# SensorSchem.net
KiCad netlist of a schematic drawn in Altium Designer
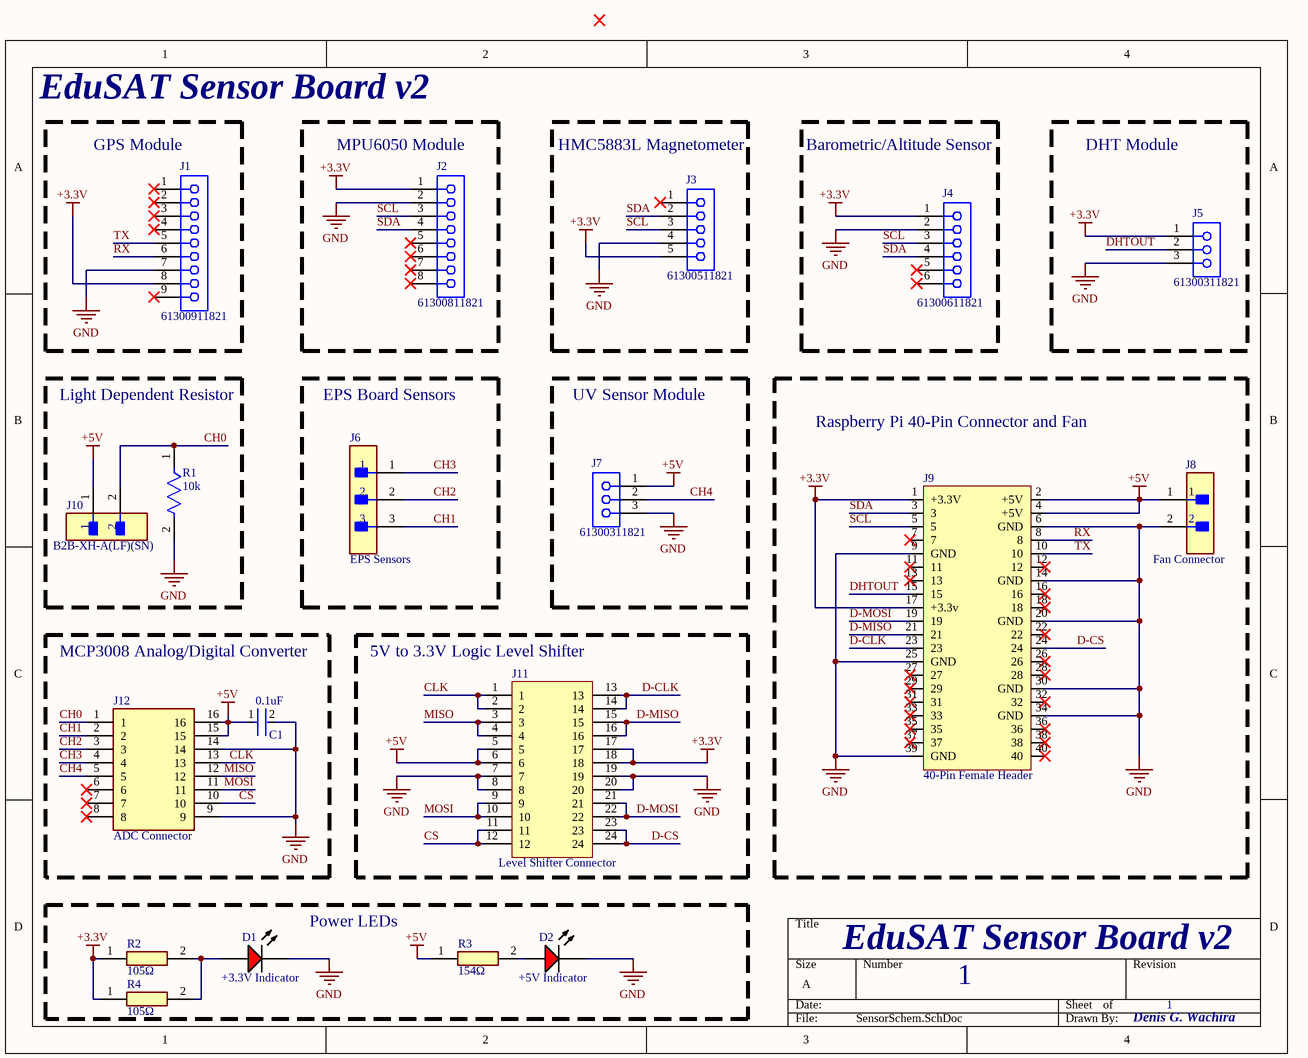
[diagram p0: SensorSchem.SchDoc]

(export (version "E")
  (design (tool "Eeschema 10.0.6"))
  (components
    (comp (ref "C1")
      (value "0.1uF")
      (footprint "FP-CL21-IPC_A")
      (description "50V 0.1uF X7R ±10% 0805 Multilayer Ceramic Capacitors MLCC - SMD/SMT ROHS TCC0805X7R104K500DT")
      (fields (field (name "TOLERANCE") "10%"))
      (libsource (lib "Altium Content Vault") (part "b4654b650e69147ec39a6b967a45e02"))
    )
    (comp (ref "D1")
      (value "+3.3V Indicator")
      (footprint "LTST-C170KRKT_V")
      (description "LED Red,KT-0805R")
      (fields (field (name "MANUFACTURER") "Lite-On"))
      (libsource (lib "Altium Content Vault") (part "LED-RED-AK-2"))
    )
    (comp (ref "D2")
      (value "+5V Indicator")
      (footprint "LTST-C170KRKT_V")
      (description "LED Red,KT-0805R")
      (fields (field (name "MANUFACTURER") "Lite-On"))
      (libsource (lib "Altium Content Vault") (part "LED-RED-AK-2"))
    )
    (comp (ref "J1")
      (value "61300911821")
      (footprint "61300911821")
      (libsource (lib "Altium Content Vault") (part "Header_Female_1R_09P"))
    )
    (comp (ref "J2")
      (value "61300811821")
      (footprint "61300811821")
      (libsource (lib "Altium Content Vault") (part "Header_Female_1R_08P"))
    )
    (comp (ref "J3")
      (value "61300511821")
      (footprint "61300511821")
      (libsource (lib "Altium Content Vault") (part "Header_Female_1R_05P"))
    )
    (comp (ref "J4")
      (value "61300611821")
      (footprint "61300611821")
      (libsource (lib "Altium Content Vault") (part "Header_Female_1R_06P"))
    )
    (comp (ref "J5")
      (value "61300311821")
      (footprint "61300311821")
      (libsource (lib "Altium Content Vault") (part "Header_Female_1R_03P"))
    )
    (comp (ref "J6")
      (value "EPS Sensors")
      (footprint "FP-S3B-XH-A-1_LF_SN-MFG")
      (description "CONN HEADER R/A 3POS 2.5MM \r\nHCZZ0139-3")
      (libsource (lib "Altium Content Vault") (part "0d3f023dd272f625e17a2be33dea85f"))
    )
    (comp (ref "J7")
      (value "61300311821")
      (footprint "61300311821")
      (libsource (lib "Altium Content Vault") (part "Header_Female_1R_03P"))
    )
    (comp (ref "J8")
      (value "Fan Connector")
      (footprint "FP-B2B-XH-A_LF_SN-MFG")
      (description "CONN HEADER VERT 2POS 2.5MM")
      (libsource (lib "Altium Content Vault") (part "3bc925449376181038e59eaffc5286c"))
    )
    (comp (ref "J9")
      (value "40-Pin Female Header")
      (footprint "FP-7-534206-0-MFG")
      (libsource (lib "University of Nairobi") (part "40-Pin Female Header"))
    )
    (comp (ref "J10")
      (value "B2B-XH-A(LF)(SN)")
      (footprint "FP-B2B-XH-A_LF_SN-MFG")
      (description "CONN HEADER VERT 2POS 2.5MM")
      (libsource (lib "") (part "3bc925449376181038e59eaffc5286c_1"))
    )
    (comp (ref "J11")
      (value "Level Shifter Connector")
      (footprint "61301221821")
      (description "3.3V to 5V Level Shifter Connector")
      (libsource (lib "University of Nairobi") (part "Level Shifter"))
    )
    (comp (ref "J12")
      (value "ADC Connector")
      (footprint "AMPHENOL_DILB16P-223TLF")
      (description "DIP Socket, Stamped and Formed")
      (fields (field (name "MP") "DILB16P-223TLF") (field (name "MF") "Amphenol ICC (FCI)"))
      (libsource (lib "University of Nairobi") (part "DILB16P-223TLF"))
    )
    (comp (ref "R1")
      (value "10k")
      (footprint "FP-MCR10-IPC_C")
      (description "Thick Film Chip Resistor, 0805, 10kΩ, 1%, 100ppm/°C, 0.125W, 150V \r\n0805W8F1002T5E")
      (fields (field (name "TOLERANCE") "1%"))
      (libsource (lib "Altium Content Vault") (part "1029c3af85768c4190bb7ad29bc67b5"))
    )
    (comp (ref "R2")
      (value "105Ω")
      (footprint "SamacSys:RESC2012X65N")
      (fields (field (name "MANUFACTURER_PART_NUMBER") "AECR0805F27R0K9"))
      (libsource (lib "*") (part "AECR0805F27R0K9"))
    )
    (comp (ref "R3")
      (value "154Ω")
      (footprint "SamacSys:RESC2012X65N")
      (fields (field (name "MANUFACTURER_PART_NUMBER") "AECR0805F27R0K9"))
      (libsource (lib "*") (part "AECR0805F27R0K9"))
    )
    (comp (ref "R4")
      (value "105Ω")
      (footprint "SamacSys:RESC2012X65N")
      (fields (field (name "MANUFACTURER_PART_NUMBER") "AECR0805F27R0K9"))
      (libsource (lib "*") (part "AECR0805F27R0K9"))
    )
  )
  (nets
    (net (code "1") (name "+3.3V") (class "Default")
      (node (ref "J1") (pin "8") (pinfunction "8_8") (pintype "passive"))
      (node (ref "J11") (pin "17") (pinfunction "17_17") (pintype "passive"))
      (node (ref "J11") (pin "18") (pinfunction "18_18") (pintype "passive"))
      (node (ref "J2") (pin "1") (pinfunction "1_1") (pintype "passive"))
      (node (ref "J3") (pin "5") (pinfunction "5_5") (pintype "passive"))
      (node (ref "J4") (pin "1") (pinfunction "1_1") (pintype "passive"))
      (node (ref "J5") (pin "1") (pinfunction "1_1") (pintype "passive"))
      (node (ref "J9") (pin "1") (pinfunction "+3.3V_1") (pintype "passive"))
      (node (ref "J9") (pin "17") (pinfunction "+3.3v_17") (pintype "passive"))
      (node (ref "R2") (pin "1") (pinfunction "1_1") (pintype "passive"))
      (node (ref "R4") (pin "1") (pinfunction "1_1") (pintype "passive"))
    )
    (net (code "2") (name "+5V") (class "Default")
      (node (ref "C1") (pin "1") (pinfunction "1_1") (pintype "passive"))
      (node (ref "J10") (pin "1") (pinfunction "1_1") (pintype "passive"))
      (node (ref "J11") (pin "5") (pinfunction "5_5") (pintype "passive"))
      (node (ref "J11") (pin "6") (pinfunction "6_6") (pintype "passive"))
      (node (ref "J12") (pin "15") (pinfunction "15_15") (pintype "passive"))
      (node (ref "J12") (pin "16") (pinfunction "16_16") (pintype "passive"))
      (node (ref "J7") (pin "1") (pinfunction "1_1") (pintype "passive"))
      (node (ref "J8") (pin "1") (pinfunction "1_1") (pintype "passive"))
      (node (ref "J9") (pin "2") (pinfunction "+5V_2") (pintype "passive"))
      (node (ref "J9") (pin "4") (pinfunction "+5V_4") (pintype "passive"))
      (node (ref "R3") (pin "1") (pinfunction "1_1") (pintype "passive"))
    )
    (net (code "3") (name "/CH0") (class "Default")
      (node (ref "J10") (pin "2") (pinfunction "2_2") (pintype "passive"))
      (node (ref "J12") (pin "1") (pinfunction "1_1") (pintype "passive"))
      (node (ref "R1") (pin "1") (pinfunction "1_1") (pintype "passive"))
    )
    (net (code "4") (name "/CH1") (class "Default")
      (node (ref "J12") (pin "2") (pinfunction "2_2") (pintype "passive"))
      (node (ref "J6") (pin "3") (pinfunction "3_3") (pintype "passive"))
    )
    (net (code "5") (name "/CH2") (class "Default")
      (node (ref "J12") (pin "3") (pinfunction "3_3") (pintype "passive"))
      (node (ref "J6") (pin "2") (pinfunction "2_2") (pintype "passive"))
    )
    (net (code "6") (name "/CH3") (class "Default")
      (node (ref "J12") (pin "4") (pinfunction "4_4") (pintype "passive"))
      (node (ref "J6") (pin "1") (pinfunction "1_1") (pintype "passive"))
    )
    (net (code "7") (name "/CH4") (class "Default")
      (node (ref "J12") (pin "5") (pinfunction "5_5") (pintype "passive"))
      (node (ref "J7") (pin "2") (pinfunction "2_2") (pintype "passive"))
    )
    (net (code "8") (name "/CLK") (class "Default")
      (node (ref "J11") (pin "1") (pinfunction "1_1") (pintype "passive"))
      (node (ref "J11") (pin "2") (pinfunction "2_2") (pintype "passive"))
      (node (ref "J12") (pin "13") (pinfunction "13_13") (pintype "passive"))
    )
    (net (code "9") (name "/CS") (class "Default")
      (node (ref "J11") (pin "11") (pinfunction "11_11") (pintype "passive"))
      (node (ref "J11") (pin "12") (pinfunction "12_12") (pintype "passive"))
      (node (ref "J12") (pin "10") (pinfunction "10_10") (pintype "passive"))
    )
    (net (code "10") (name "/D-CLK") (class "Default")
      (node (ref "J11") (pin "13") (pinfunction "13_13") (pintype "passive"))
      (node (ref "J11") (pin "14") (pinfunction "14_14") (pintype "passive"))
      (node (ref "J9") (pin "23") (pinfunction "23_23") (pintype "passive"))
    )
    (net (code "11") (name "/D-CS") (class "Default")
      (node (ref "J11") (pin "23") (pinfunction "23_23") (pintype "passive"))
      (node (ref "J11") (pin "24") (pinfunction "24_24") (pintype "passive"))
      (node (ref "J9") (pin "24") (pinfunction "24_24") (pintype "passive"))
    )
    (net (code "12") (name "/D-MISO") (class "Default")
      (node (ref "J11") (pin "15") (pinfunction "15_15") (pintype "passive"))
      (node (ref "J11") (pin "16") (pinfunction "16_16") (pintype "passive"))
      (node (ref "J9") (pin "21") (pinfunction "21_21") (pintype "passive"))
    )
    (net (code "13") (name "/D-MOSI") (class "Default")
      (node (ref "J11") (pin "21") (pinfunction "21_21") (pintype "passive"))
      (node (ref "J11") (pin "22") (pinfunction "22_22") (pintype "passive"))
      (node (ref "J9") (pin "19") (pinfunction "19_19") (pintype "passive"))
    )
    (net (code "14") (name "/DHTOUT") (class "Default")
      (node (ref "J5") (pin "2") (pinfunction "2_2") (pintype "passive"))
      (node (ref "J9") (pin "15") (pinfunction "15_15") (pintype "passive"))
    )
    (net (code "15") (name "/MISO") (class "Default")
      (node (ref "J11") (pin "3") (pinfunction "3_3") (pintype "passive"))
      (node (ref "J11") (pin "4") (pinfunction "4_4") (pintype "passive"))
      (node (ref "J12") (pin "12") (pinfunction "12_12") (pintype "passive"))
    )
    (net (code "16") (name "/MOSI") (class "Default")
      (node (ref "J11") (pin "10") (pinfunction "10_10") (pintype "passive"))
      (node (ref "J11") (pin "9") (pinfunction "9_9") (pintype "passive"))
      (node (ref "J12") (pin "11") (pinfunction "11_11") (pintype "passive"))
    )
    (net (code "17") (name "/RX") (class "Default")
      (node (ref "J1") (pin "6") (pinfunction "6_6") (pintype "passive"))
      (node (ref "J9") (pin "8") (pinfunction "8_8") (pintype "passive"))
    )
    (net (code "18") (name "/SCL") (class "Default")
      (node (ref "J2") (pin "3") (pinfunction "3_3") (pintype "passive"))
      (node (ref "J3") (pin "3") (pinfunction "3_3") (pintype "passive"))
      (node (ref "J4") (pin "3") (pinfunction "3_3") (pintype "passive"))
      (node (ref "J9") (pin "5") (pinfunction "5_5") (pintype "passive"))
    )
    (net (code "19") (name "/SDA") (class "Default")
      (node (ref "J2") (pin "4") (pinfunction "4_4") (pintype "passive"))
      (node (ref "J3") (pin "2") (pinfunction "2_2") (pintype "passive"))
      (node (ref "J4") (pin "4") (pinfunction "4_4") (pintype "passive"))
      (node (ref "J9") (pin "3") (pinfunction "3_3") (pintype "passive"))
    )
    (net (code "20") (name "/TX") (class "Default")
      (node (ref "J1") (pin "5") (pinfunction "5_5") (pintype "passive"))
      (node (ref "J9") (pin "10") (pinfunction "10_10") (pintype "passive"))
    )
    (net (code "21") (name "GND") (class "Default")
      (node (ref "C1") (pin "2") (pinfunction "2_2") (pintype "passive"))
      (node (ref "D1") (pin "2") (pinfunction "K_2") (pintype "passive"))
      (node (ref "D2") (pin "2") (pinfunction "K_2") (pintype "passive"))
      (node (ref "J1") (pin "7") (pinfunction "7_7") (pintype "passive"))
      (node (ref "J11") (pin "19") (pinfunction "19_19") (pintype "passive"))
      (node (ref "J11") (pin "20") (pinfunction "20_20") (pintype "passive"))
      (node (ref "J11") (pin "7") (pinfunction "7_7") (pintype "passive"))
      (node (ref "J11") (pin "8") (pinfunction "8_8") (pintype "passive"))
      (node (ref "J12") (pin "14") (pinfunction "14_14") (pintype "passive"))
      (node (ref "J12") (pin "9") (pinfunction "9_9") (pintype "passive"))
      (node (ref "J2") (pin "2") (pinfunction "2_2") (pintype "passive"))
      (node (ref "J3") (pin "4") (pinfunction "4_4") (pintype "passive"))
      (node (ref "J4") (pin "2") (pinfunction "2_2") (pintype "passive"))
      (node (ref "J5") (pin "3") (pinfunction "3_3") (pintype "passive"))
      (node (ref "J7") (pin "3") (pinfunction "3_3") (pintype "passive"))
      (node (ref "J8") (pin "2") (pinfunction "2_2") (pintype "passive"))
      (node (ref "J9") (pin "14") (pinfunction "GND_14") (pintype "passive"))
      (node (ref "J9") (pin "20") (pinfunction "GND_20") (pintype "passive"))
      (node (ref "J9") (pin "25") (pinfunction "GND_25") (pintype "passive"))
      (node (ref "J9") (pin "30") (pinfunction "GND_30") (pintype "passive"))
      (node (ref "J9") (pin "34") (pinfunction "GND_34") (pintype "passive"))
      (node (ref "J9") (pin "39") (pinfunction "GND_39") (pintype "passive"))
      (node (ref "J9") (pin "6") (pinfunction "GND_6") (pintype "passive"))
      (node (ref "J9") (pin "9") (pinfunction "GND_9") (pintype "passive"))
      (node (ref "R1") (pin "2") (pinfunction "2_2") (pintype "passive"))
    )
    (net (code "22") (name "Net-(D1-A)") (class "Default")
      (node (ref "D1") (pin "1") (pinfunction "A_1") (pintype "passive"))
      (node (ref "R2") (pin "2") (pinfunction "2_2") (pintype "passive"))
      (node (ref "R4") (pin "2") (pinfunction "2_2") (pintype "passive"))
    )
    (net (code "23") (name "Net-(D2-A)") (class "Default")
      (node (ref "D2") (pin "1") (pinfunction "A_1") (pintype "passive"))
      (node (ref "R3") (pin "2") (pinfunction "2_2") (pintype "passive"))
    )
    (net (code "24") (name "unconnected-(J1-Pad1)") (class "Default")
      (node (ref "J1") (pin "1") (pinfunction "1_1") (pintype "passive+no_connect"))
    )
    (net (code "25") (name "unconnected-(J1-Pad2)") (class "Default")
      (node (ref "J1") (pin "2") (pinfunction "2_2") (pintype "passive+no_connect"))
    )
    (net (code "26") (name "unconnected-(J1-Pad3)") (class "Default")
      (node (ref "J1") (pin "3") (pinfunction "3_3") (pintype "passive+no_connect"))
    )
    (net (code "27") (name "unconnected-(J1-Pad4)") (class "Default")
      (node (ref "J1") (pin "4") (pinfunction "4_4") (pintype "passive+no_connect"))
    )
    (net (code "28") (name "unconnected-(J1-Pad9)") (class "Default")
      (node (ref "J1") (pin "9") (pinfunction "9_9") (pintype "passive+no_connect"))
    )
    (net (code "29") (name "unconnected-(J2-Pad5)") (class "Default")
      (node (ref "J2") (pin "5") (pinfunction "5_5") (pintype "passive+no_connect"))
    )
    (net (code "30") (name "unconnected-(J2-Pad6)") (class "Default")
      (node (ref "J2") (pin "6") (pinfunction "6_6") (pintype "passive+no_connect"))
    )
    (net (code "31") (name "unconnected-(J2-Pad7)") (class "Default")
      (node (ref "J2") (pin "7") (pinfunction "7_7") (pintype "passive+no_connect"))
    )
    (net (code "32") (name "unconnected-(J2-Pad8)") (class "Default")
      (node (ref "J2") (pin "8") (pinfunction "8_8") (pintype "passive+no_connect"))
    )
    (net (code "33") (name "unconnected-(J3-Pad1)") (class "Default")
      (node (ref "J3") (pin "1") (pinfunction "1_1") (pintype "passive+no_connect"))
    )
    (net (code "34") (name "unconnected-(J4-Pad5)") (class "Default")
      (node (ref "J4") (pin "5") (pinfunction "5_5") (pintype "passive+no_connect"))
    )
    (net (code "35") (name "unconnected-(J4-Pad6)") (class "Default")
      (node (ref "J4") (pin "6") (pinfunction "6_6") (pintype "passive+no_connect"))
    )
    (net (code "36") (name "unconnected-(J9-Pad7)") (class "Default")
      (node (ref "J9") (pin "7") (pinfunction "7_7") (pintype "passive+no_connect"))
    )
    (net (code "37") (name "unconnected-(J9-Pad11)") (class "Default")
      (node (ref "J9") (pin "11") (pinfunction "11_11") (pintype "passive+no_connect"))
    )
    (net (code "38") (name "unconnected-(J9-Pad12)") (class "Default")
      (node (ref "J9") (pin "12") (pinfunction "12_12") (pintype "passive+no_connect"))
    )
    (net (code "39") (name "unconnected-(J9-Pad13)") (class "Default")
      (node (ref "J9") (pin "13") (pinfunction "13_13") (pintype "passive+no_connect"))
    )
    (net (code "40") (name "unconnected-(J9-Pad16)") (class "Default")
      (node (ref "J9") (pin "16") (pinfunction "16_16") (pintype "passive+no_connect"))
    )
    (net (code "41") (name "unconnected-(J9-Pad18)") (class "Default")
      (node (ref "J9") (pin "18") (pinfunction "18_18") (pintype "passive+no_connect"))
    )
    (net (code "42") (name "unconnected-(J9-Pad22)") (class "Default")
      (node (ref "J9") (pin "22") (pinfunction "22_22") (pintype "passive+no_connect"))
    )
    (net (code "43") (name "unconnected-(J9-Pad26)") (class "Default")
      (node (ref "J9") (pin "26") (pinfunction "26_26") (pintype "passive+no_connect"))
    )
    (net (code "44") (name "unconnected-(J9-Pad27)") (class "Default")
      (node (ref "J9") (pin "27") (pinfunction "27_27") (pintype "passive+no_connect"))
    )
    (net (code "45") (name "unconnected-(J9-Pad28)") (class "Default")
      (node (ref "J9") (pin "28") (pinfunction "28_28") (pintype "passive+no_connect"))
    )
    (net (code "46") (name "unconnected-(J9-Pad29)") (class "Default")
      (node (ref "J9") (pin "29") (pinfunction "29_29") (pintype "passive+no_connect"))
    )
    (net (code "47") (name "unconnected-(J9-Pad31)") (class "Default")
      (node (ref "J9") (pin "31") (pinfunction "31_31") (pintype "passive+no_connect"))
    )
    (net (code "48") (name "unconnected-(J9-Pad32)") (class "Default")
      (node (ref "J9") (pin "32") (pinfunction "32_32") (pintype "passive+no_connect"))
    )
    (net (code "49") (name "unconnected-(J9-Pad33)") (class "Default")
      (node (ref "J9") (pin "33") (pinfunction "33_33") (pintype "passive+no_connect"))
    )
    (net (code "50") (name "unconnected-(J9-Pad35)") (class "Default")
      (node (ref "J9") (pin "35") (pinfunction "35_35") (pintype "passive+no_connect"))
    )
    (net (code "51") (name "unconnected-(J9-Pad36)") (class "Default")
      (node (ref "J9") (pin "36") (pinfunction "36_36") (pintype "passive+no_connect"))
    )
    (net (code "52") (name "unconnected-(J9-Pad37)") (class "Default")
      (node (ref "J9") (pin "37") (pinfunction "37_37") (pintype "passive+no_connect"))
    )
    (net (code "53") (name "unconnected-(J9-Pad38)") (class "Default")
      (node (ref "J9") (pin "38") (pinfunction "38_38") (pintype "passive+no_connect"))
    )
    (net (code "54") (name "unconnected-(J9-Pad40)") (class "Default")
      (node (ref "J9") (pin "40") (pinfunction "40_40") (pintype "passive+no_connect"))
    )
    (net (code "55") (name "unconnected-(J12-Pad6)") (class "Default")
      (node (ref "J12") (pin "6") (pinfunction "6_6") (pintype "passive+no_connect"))
    )
    (net (code "56") (name "unconnected-(J12-Pad7)") (class "Default")
      (node (ref "J12") (pin "7") (pinfunction "7_7") (pintype "passive+no_connect"))
    )
    (net (code "57") (name "unconnected-(J12-Pad8)") (class "Default")
      (node (ref "J12") (pin "8") (pinfunction "8_8") (pintype "passive+no_connect"))
    )
  )
)
